# Communication.net
KiCad netlist of a schematic drawn in Altium Designer
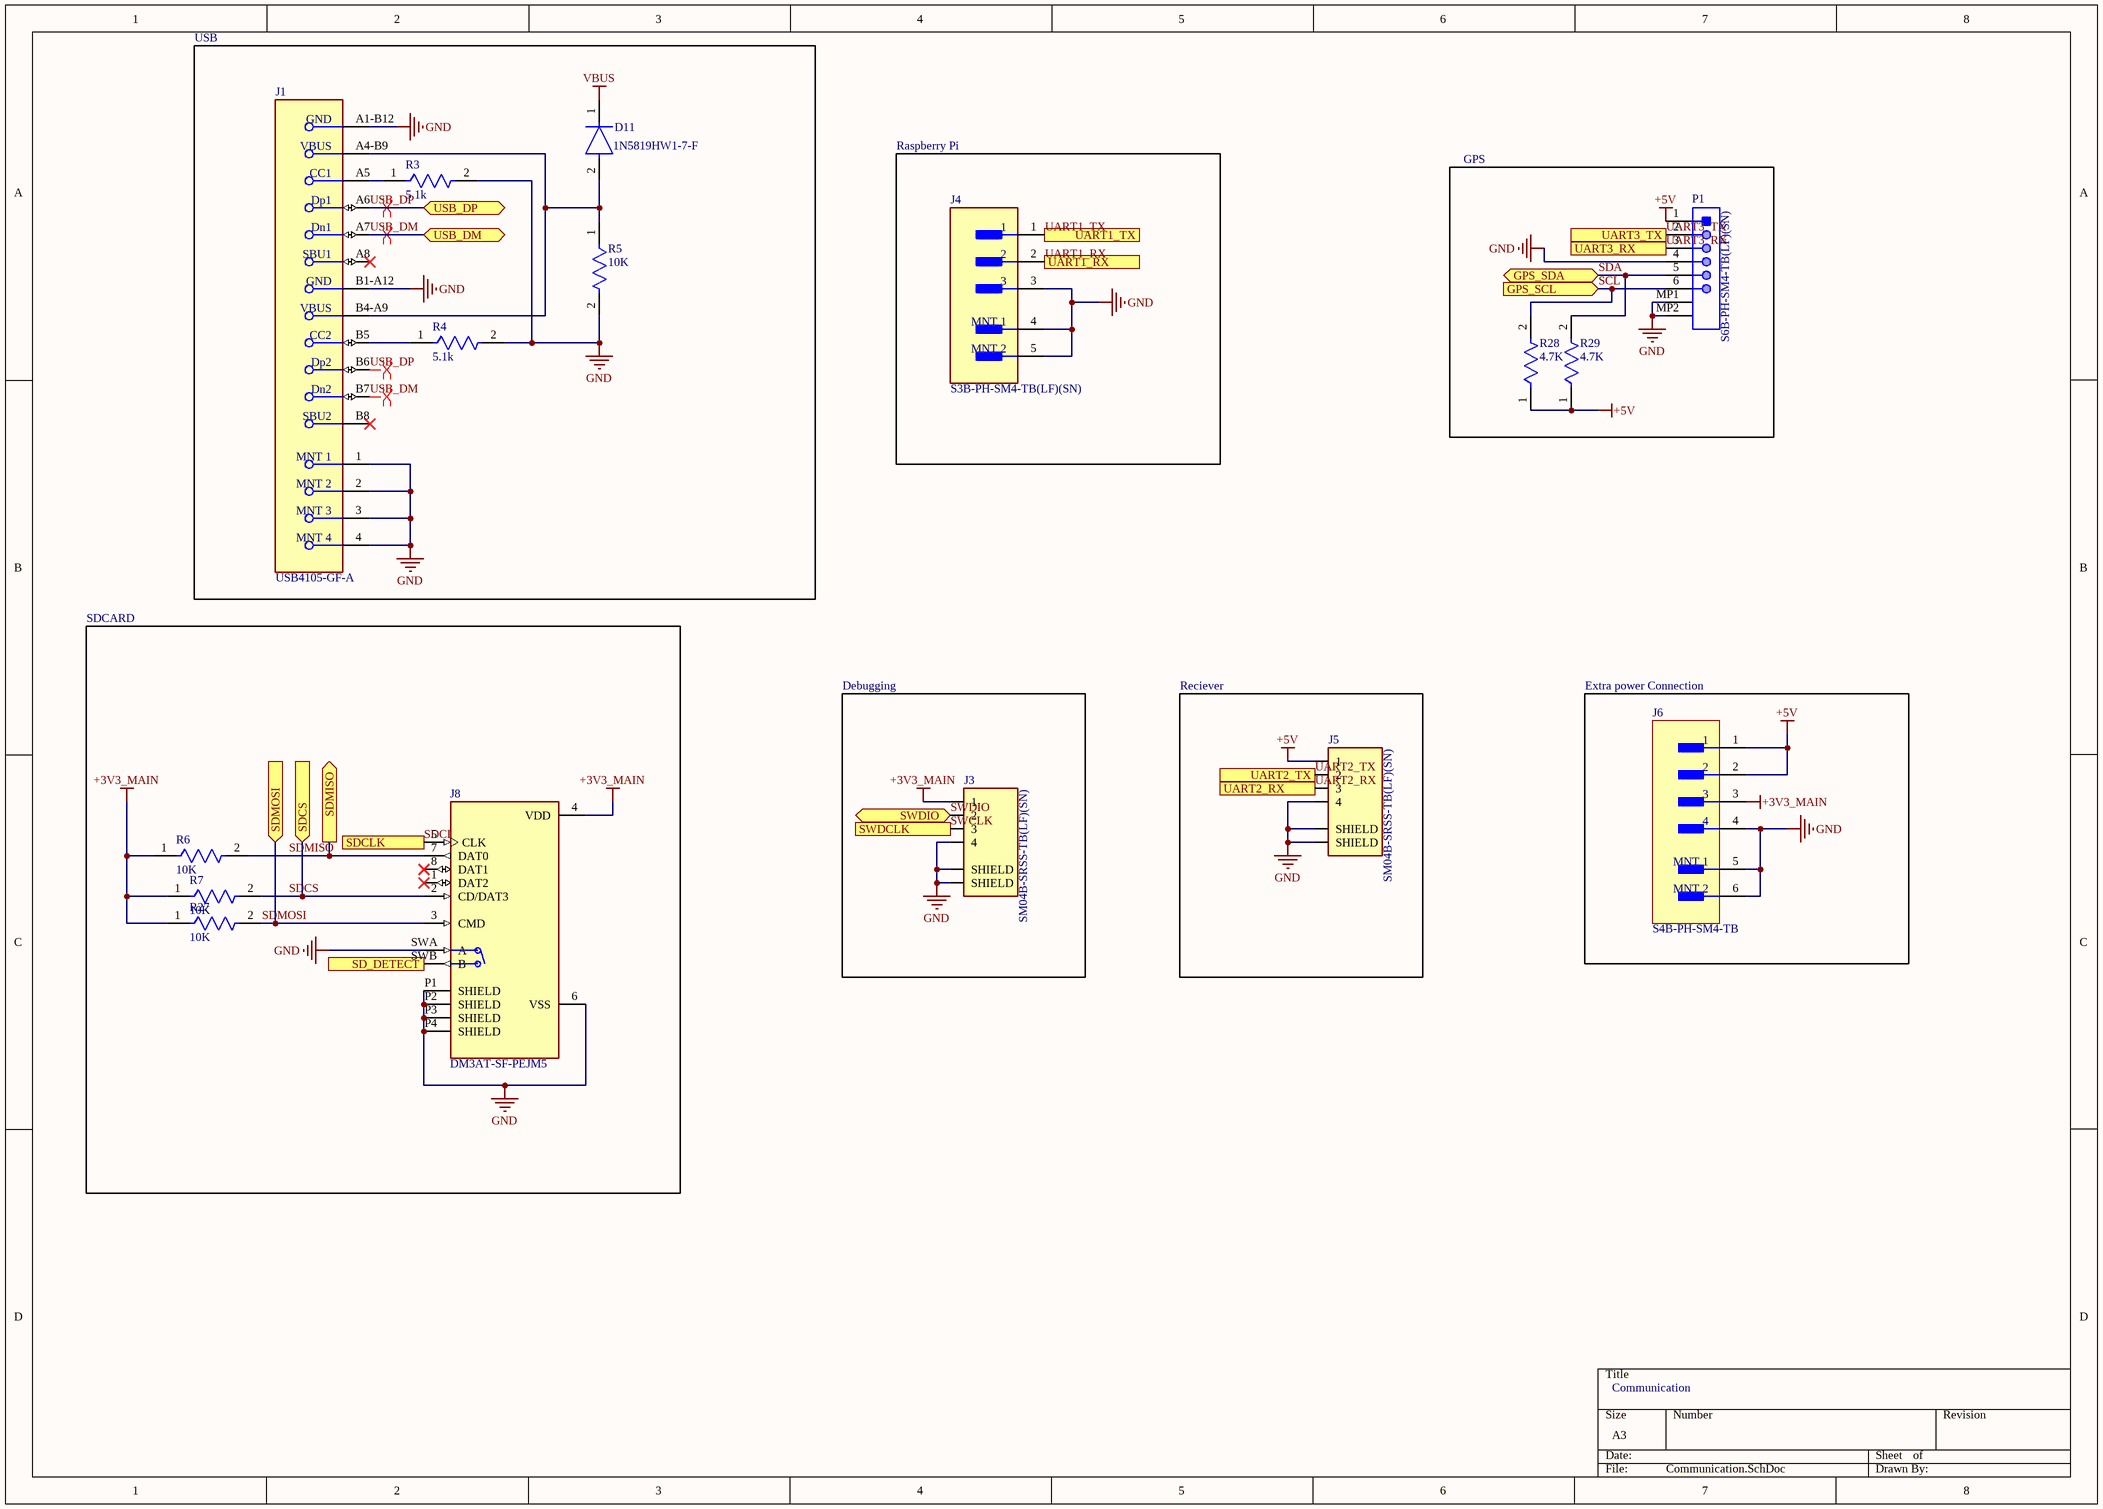
[diagram p0: Communication.SchDoc]

(export (version "E")
  (design (tool "Eeschema 10.0.6"))
  (components
    (comp (ref "D11")
      (value "1N5819HW1-7-F")
      (footprint "FP-SOD123F_Type_B-MFG")
      (description "DIODE SBR 40V 1A SOD123F")
      (fields
        (field (name "MANUFACTURER") "Diodes Inc.")
        (field (name "OCTOPART") "https://octopart.com/1n5819hw1-7-f-diodes+inc.-67250096")
      )
      (libsource (lib "Altium Content Vault") (part "d7152d700b627762746794eb795d46e"))
    )
    (comp (ref "J1")
      (value "USB4105-GF-A")
      (footprint "FP-USB4105-GF-A-MFG")
      (description "CONN RCPT USB2.0 TYPEC 5A")
      (fields
        (field (name "MANUFACTURER") "GCT")
        (field (name "OCTOPART") "https://octopart.com/usb4105-gf-a-gct-106627878")
      )
      (libsource (lib "Altium Content Vault") (part "e7c17a616881a82b79941196b4bec10"))
    )
    (comp (ref "J3")
      (value "SM04B-SRSS-TB(LF)(SN)")
      (footprint "JST_SM04B-SRSS-TB(LF)(SN)")
      (description "Connector Header Surface Mount, Right Angle 4 position 0.039 (1.00mm)")
      (fields (field (name "MF") "JST Sales"))
      (libsource (lib "SM04B-SRSS-TB_LF__SN_(4PIN SH SERIES)") (part "SM04B-SRSS-TB(LF)(SN)"))
    )
    (comp (ref "J4")
      (value "S3B-PH-SM4-TB(LF)(SN)")
      (footprint "FP-S3B-PH-SM4-TB_LF_SN-MFG")
      (description "CONN HEADER SMD R/A 3POS 2MM")
      (libsource (lib "Altium Content Vault") (part "38689d6f3df0f9b234c6ddcef280d85"))
    )
    (comp (ref "J5")
      (value "SM04B-SRSS-TB(LF)(SN)")
      (footprint "JST_SM04B-SRSS-TB(LF)(SN)")
      (description "Connector Header Surface Mount, Right Angle 4 position 0.039 (1.00mm)")
      (fields (field (name "MF") "JST Sales"))
      (libsource (lib "SM04B-SRSS-TB_LF__SN_(4PIN SH SERIES)") (part "SM04B-SRSS-TB(LF)(SN)"))
    )
    (comp (ref "J6")
      (value "S4B-PH-SM4-TB")
      (footprint "FP-S4B-PH-SM4-TB-MFG")
      (description "S4B-PH-SM4-TB Header S4B-PH-SM4-TB, 2.00mm, 4-contacts, side entry, SMT, /1000/reel")
      (libsource (lib "Altium Content Vault") (part "S4B-PH-SM4-TB"))
    )
    (comp (ref "J8")
      (value "DM3AT-SF-PEJM5")
      (footprint "HRS_DM3AT-SF-PEJM5")
      (description "10 (8 + 2) Position Card Connector Secure Digital - microSDâ„¢ Surface Mount, Right Angle Gold")
      (fields (field (name "MF") "Hirose"))
      (libsource (lib "DM3AT-SF-PEJM5 pushpull") (part "DM3AT-SF-PEJM5"))
    )
    (comp (ref "P1")
      (value "S6B-PH-SM4-TB(LF)(SN)")
      (footprint "JST-S6B-PH-SM4-TB(LF)(SN)_V")
      (description "Male Header, Pitch 2 mm, 1 x 6 Position, Height 5.5 mm, -25 to 85 degC")
      (fields (field (name "MANUFACTURER") "JST"))
      (libsource (lib "Altium Content Vault") (part "CN-1P-2M-R6"))
    )
    (comp (ref "R3")
      (value "5.1k")
      (footprint "FP-RN73R1E-IPC_C")
      (description "5.1kΩ ±1% 0.063W, 1/16W Chip Resistor 0402 (1005 Metric) Moisture Resistant Thin Film")
      (libsource (lib "Altium Content Vault") (part "1029c3af85768c4190bb7ad29bc67b5"))
    )
    (comp (ref "R4")
      (value "5.1k")
      (footprint "FP-RN73R1E-IPC_C")
      (description "5.1kΩ ±1% 0.063W, 1/16W Chip Resistor 0402 (1005 Metric) Moisture Resistant Thin Film")
      (libsource (lib "Altium Content Vault") (part "1029c3af85768c4190bb7ad29bc67b5"))
    )
    (comp (ref "R5")
      (value "10K")
      (footprint "FP-MCS0402-MFG")
      (description "RES SMD 1.2K OHM 1% 1/10W 0402")
      (fields (field (name "TOLERANCE") "0.5%"))
      (libsource (lib "Altium Content Vault") (part "1029c3af85768c4190bb7ad29bc67b5"))
    )
    (comp (ref "R6")
      (value "10K")
      (footprint "FP-MCS0402-MFG")
      (description "RES SMD 1.2K OHM 1% 1/10W 0402")
      (fields (field (name "TOLERANCE") "0.5%"))
      (libsource (lib "Altium Content Vault") (part "1029c3af85768c4190bb7ad29bc67b5"))
    )
    (comp (ref "R7")
      (value "10K")
      (footprint "FP-MCS0402-MFG")
      (description "RES SMD 1.2K OHM 1% 1/10W 0402")
      (fields (field (name "TOLERANCE") "0.5%"))
      (libsource (lib "Altium Content Vault") (part "1029c3af85768c4190bb7ad29bc67b5"))
    )
    (comp (ref "R27")
      (value "10K")
      (footprint "FP-MCS0402-MFG")
      (description "RES SMD 1.2K OHM 1% 1/10W 0402")
      (fields (field (name "TOLERANCE") "0.5%"))
      (libsource (lib "Altium Content Vault") (part "1029c3af85768c4190bb7ad29bc67b5"))
    )
    (comp (ref "R28")
      (value "4.7K")
      (footprint "FP-CRCW0402-Pe3-IPC_C")
      (description "RES Thick Film, 4.7kΩ, 1%, 0.063W, 50ppm/°C, 0402")
      (fields (field (name "TOLERANCE") "1%"))
      (libsource (lib "Altium Content Vault") (part "1029c3af85768c4190bb7ad29bc67b5"))
    )
    (comp (ref "R29")
      (value "4.7K")
      (footprint "FP-CRCW0402-Pe3-IPC_C")
      (description "RES Thick Film, 4.7kΩ, 1%, 0.063W, 50ppm/°C, 0402")
      (fields (field (name "TOLERANCE") "1%"))
      (libsource (lib "Altium Content Vault") (part "1029c3af85768c4190bb7ad29bc67b5"))
    )
  )
  (nets
    (net (code "1") (name "+3V3_MAIN") (class "Default")
      (node (ref "J3") (pin "1") (pinfunction "1_1") (pintype "passive"))
      (node (ref "J6") (pin "3") (pinfunction "3_3") (pintype "passive"))
      (node (ref "J8") (pin "4") (pinfunction "VDD_4") (pintype "power_in"))
      (node (ref "R27") (pin "1") (pinfunction "1_1") (pintype "passive"))
      (node (ref "R6") (pin "1") (pinfunction "1_1") (pintype "passive"))
      (node (ref "R7") (pin "1") (pinfunction "1_1") (pintype "passive"))
    )
    (net (code "2") (name "+5V") (class "Default")
      (node (ref "J5") (pin "1") (pinfunction "1_1") (pintype "passive"))
      (node (ref "J6") (pin "1") (pinfunction "1_1") (pintype "passive"))
      (node (ref "J6") (pin "2") (pinfunction "2_2") (pintype "passive"))
      (node (ref "P1") (pin "1") (pinfunction "1_1") (pintype "passive"))
      (node (ref "R28") (pin "1") (pinfunction "1_1") (pintype "passive"))
      (node (ref "R29") (pin "1") (pinfunction "1_1") (pintype "passive"))
    )
    (net (code "3") (name "/SCL") (class "Default")
      (node (ref "P1") (pin "6") (pinfunction "6_6") (pintype "passive"))
      (node (ref "R28") (pin "2") (pinfunction "2_2") (pintype "passive"))
    )
    (net (code "4") (name "/SDA") (class "Default")
      (node (ref "P1") (pin "5") (pinfunction "5_5") (pintype "passive"))
      (node (ref "R29") (pin "2") (pinfunction "2_2") (pintype "passive"))
    )
    (net (code "5") (name "/SDCLK") (class "Default")
      (node (ref "J8") (pin "5") (pinfunction "CLK_5") (pintype "input"))
    )
    (net (code "6") (name "/SDCS") (class "Default")
      (node (ref "J8") (pin "2") (pinfunction "CD/DAT3_2") (pintype "input"))
      (node (ref "R7") (pin "2") (pinfunction "2_2") (pintype "passive"))
    )
    (net (code "7") (name "/SDMISO") (class "Default")
      (node (ref "J8") (pin "7") (pinfunction "DAT0_7") (pintype "output"))
      (node (ref "R6") (pin "2") (pinfunction "2_2") (pintype "passive"))
    )
    (net (code "8") (name "/SDMOSI") (class "Default")
      (node (ref "J8") (pin "3") (pinfunction "CMD_3") (pintype "input"))
      (node (ref "R27") (pin "2") (pinfunction "2_2") (pintype "passive"))
    )
    (net (code "9") (name "/SD_DETECT") (class "Default")
      (node (ref "J8") (pin "SWB") (pinfunction "B_SWB") (pintype "output"))
    )
    (net (code "10") (name "/SWCLK") (class "Default")
      (node (ref "J3") (pin "3") (pinfunction "3_3") (pintype "passive"))
    )
    (net (code "11") (name "/SWDIO") (class "Default")
      (node (ref "J3") (pin "2") (pinfunction "2_2") (pintype "passive"))
    )
    (net (code "12") (name "/UART1_RX") (class "Default")
      (node (ref "J4") (pin "2") (pinfunction "2_2") (pintype "passive"))
    )
    (net (code "13") (name "/UART1_TX") (class "Default")
      (node (ref "J4") (pin "1") (pinfunction "1_1") (pintype "passive"))
    )
    (net (code "14") (name "/UART2_RX") (class "Default")
      (node (ref "J5") (pin "3") (pinfunction "3_3") (pintype "passive"))
    )
    (net (code "15") (name "/UART2_TX") (class "Default")
      (node (ref "J5") (pin "2") (pinfunction "2_2") (pintype "passive"))
    )
    (net (code "16") (name "/UART3_RX") (class "Default")
      (node (ref "P1") (pin "3") (pinfunction "3_3") (pintype "passive"))
    )
    (net (code "17") (name "/UART3_TX") (class "Default")
      (node (ref "P1") (pin "2") (pinfunction "2_2") (pintype "passive"))
    )
    (net (code "18") (name "/USB_DM") (class "Default")
      (node (ref "J1") (pin "A7") (pinfunction "Dn1_A7") (pintype "bidirectional"))
      (node (ref "J1") (pin "B7") (pinfunction "Dn2_B7") (pintype "bidirectional"))
    )
    (net (code "19") (name "/USB_DP") (class "Default")
      (node (ref "J1") (pin "A6") (pinfunction "Dp1_A6") (pintype "bidirectional"))
      (node (ref "J1") (pin "B6") (pinfunction "Dp2_B6") (pintype "bidirectional"))
    )
    (net (code "20") (name "GND") (class "Default")
      (node (ref "J1") (pin "1") (pinfunction "MNT_1_1") (pintype "power_in"))
      (node (ref "J1") (pin "2") (pinfunction "MNT_2_2") (pintype "power_in"))
      (node (ref "J1") (pin "3") (pinfunction "MNT_3_3") (pintype "power_in"))
      (node (ref "J1") (pin "4") (pinfunction "MNT_4_4") (pintype "power_in"))
      (node (ref "J1") (pin "A1-B12") (pinfunction "GND_A1-B12") (pintype "power_in"))
      (node (ref "J1") (pin "B1-A12") (pinfunction "GND_B1-A12") (pintype "power_in"))
      (node (ref "J3") (pin "4") (pinfunction "4_4") (pintype "passive"))
      (node (ref "J3") (pin "S1") (pinfunction "SHIELD_S1") (pintype "passive"))
      (node (ref "J3") (pin "S2") (pinfunction "SHIELD_S2") (pintype "passive"))
      (node (ref "J4") (pin "3") (pinfunction "3_3") (pintype "passive"))
      (node (ref "J4") (pin "4") (pinfunction "MNT_1_4") (pintype "passive"))
      (node (ref "J4") (pin "5") (pinfunction "MNT_2_5") (pintype "passive"))
      (node (ref "J5") (pin "4") (pinfunction "4_4") (pintype "passive"))
      (node (ref "J5") (pin "S1") (pinfunction "SHIELD_S1") (pintype "passive"))
      (node (ref "J5") (pin "S2") (pinfunction "SHIELD_S2") (pintype "passive"))
      (node (ref "J6") (pin "4") (pinfunction "4_4") (pintype "passive"))
      (node (ref "J6") (pin "5") (pinfunction "MNT_1_5") (pintype "passive"))
      (node (ref "J6") (pin "6") (pinfunction "MNT_2_6") (pintype "passive"))
      (node (ref "J8") (pin "6") (pinfunction "VSS_6") (pintype "power_in"))
      (node (ref "J8") (pin "P1") (pinfunction "SHIELD_P1") (pintype "passive"))
      (node (ref "J8") (pin "P2") (pinfunction "SHIELD_P2") (pintype "passive"))
      (node (ref "J8") (pin "P3") (pinfunction "SHIELD_P3") (pintype "passive"))
      (node (ref "J8") (pin "P4") (pinfunction "SHIELD_P4") (pintype "passive"))
      (node (ref "J8") (pin "SWA") (pinfunction "A_SWA") (pintype "input"))
      (node (ref "P1") (pin "4") (pinfunction "4_4") (pintype "passive"))
      (node (ref "P1") (pin "MP1") (pinfunction "MP1_MP1") (pintype "passive"))
      (node (ref "P1") (pin "MP2") (pinfunction "MP2_MP2") (pintype "passive"))
      (node (ref "R3") (pin "2") (pinfunction "2_2") (pintype "passive"))
      (node (ref "R4") (pin "2") (pinfunction "2_2") (pintype "passive"))
      (node (ref "R5") (pin "2") (pinfunction "2_2") (pintype "passive"))
    )
    (net (code "21") (name "Net-(D11-A)") (class "Default")
      (node (ref "D11") (pin "2") (pinfunction "A_2") (pintype "passive"))
      (node (ref "J1") (pin "A4-B9") (pinfunction "VBUS_A4-B9") (pintype "power_in"))
      (node (ref "J1") (pin "B4-A9") (pinfunction "VBUS_B4-A9") (pintype "power_in"))
      (node (ref "R5") (pin "1") (pinfunction "1_1") (pintype "passive"))
    )
    (net (code "22") (name "Net-(J1-CC1)") (class "Default")
      (node (ref "J1") (pin "A5") (pinfunction "CC1_A5") (pintype "power_in"))
      (node (ref "R3") (pin "1") (pinfunction "1_1") (pintype "passive"))
    )
    (net (code "23") (name "Net-(J1-CC2)") (class "Default")
      (node (ref "J1") (pin "B5") (pinfunction "CC2_B5") (pintype "bidirectional"))
      (node (ref "R4") (pin "1") (pinfunction "1_1") (pintype "passive"))
    )
    (net (code "24") (name "VBUS") (class "Default")
      (node (ref "D11") (pin "1") (pinfunction "C_1") (pintype "passive"))
    )
    (net (code "25") (name "unconnected-(J1-SBU1-PadA8)") (class "Default")
      (node (ref "J1") (pin "A8") (pinfunction "SBU1_A8") (pintype "bidirectional+no_connect"))
    )
    (net (code "26") (name "unconnected-(J1-SBU2-PadB8)") (class "Default")
      (node (ref "J1") (pin "B8") (pinfunction "SBU2_B8") (pintype "power_in+no_connect"))
    )
    (net (code "27") (name "unconnected-(J8-DAT1-Pad8)") (class "Default")
      (node (ref "J8") (pin "8") (pinfunction "DAT1_8") (pintype "bidirectional+no_connect"))
    )
    (net (code "28") (name "unconnected-(J8-DAT2-Pad1)") (class "Default")
      (node (ref "J8") (pin "1") (pinfunction "DAT2_1") (pintype "bidirectional+no_connect"))
    )
  )
)
